# controller.net
KiCad netlist of a schematic drawn in EAGLE
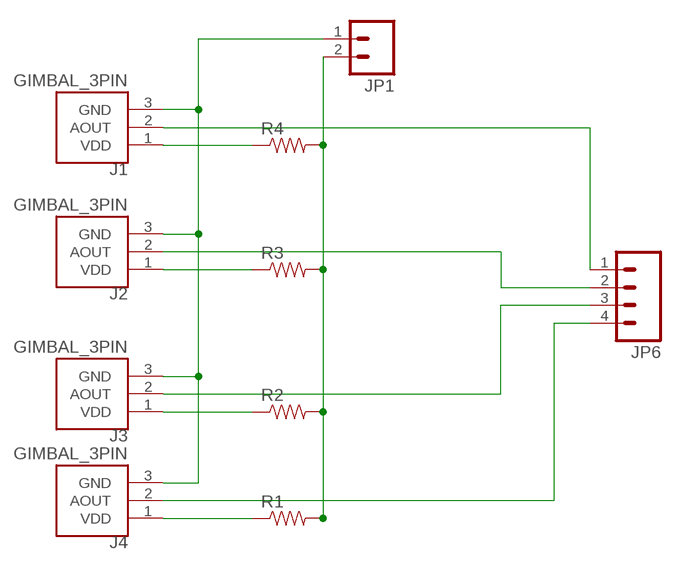
[diagram p0: schematic, sheet 1]

(export (version "E")
  (design (tool "Eeschema 10.0.6"))
  (components
    (comp (ref "J1")
      (value "GIMBAL_3PIN")
      (footprint "eagle-import:JST-3-PTH")
      (libsource (lib "eagle-import") (part "GIMBAL_3PIN"))
    )
    (comp (ref "J2")
      (value "GIMBAL_3PIN")
      (footprint "eagle-import:JST-3-PTH")
      (libsource (lib "eagle-import") (part "GIMBAL_3PIN"))
    )
    (comp (ref "J3")
      (value "GIMBAL_3PIN")
      (footprint "eagle-import:JST-3-PTH")
      (libsource (lib "eagle-import") (part "GIMBAL_3PIN"))
    )
    (comp (ref "J4")
      (value "GIMBAL_3PIN")
      (footprint "eagle-import:JST-3-PTH")
      (libsource (lib "eagle-import") (part "GIMBAL_3PIN"))
    )
    (comp (ref "JP1")
      (value "M02LOCK")
      (footprint "eagle-import:1X02_LOCK")
      (libsource (lib "eagle-import") (part "M02LOCK"))
    )
    (comp (ref "JP6")
      (value "M04PTH")
      (footprint "eagle-import:1X04")
      (libsource (lib "eagle-import") (part "M04PTH"))
    )
    (comp (ref "R1")
      (value "RESISTORPTH-1/6W")
      (footprint "eagle-import:1_6W-RES")
      (libsource (lib "eagle-import") (part "RESISTORPTH-1/6W"))
    )
    (comp (ref "R2")
      (value "RESISTORPTH-1/6W")
      (footprint "eagle-import:1_6W-RES")
      (libsource (lib "eagle-import") (part "RESISTORPTH-1/6W"))
    )
    (comp (ref "R3")
      (value "RESISTORPTH-1/6W")
      (footprint "eagle-import:1_6W-RES")
      (libsource (lib "eagle-import") (part "RESISTORPTH-1/6W"))
    )
    (comp (ref "R4")
      (value "RESISTORPTH-1/6W")
      (footprint "eagle-import:1_6W-RES")
      (libsource (lib "eagle-import") (part "RESISTORPTH-1/6W"))
    )
  )
  (nets
    (net (code "1") (name "Net-(J1-AOUT)") (class "Default")
      (node (ref "J1") (pin "2") (pinfunction "AOUT_2") (pintype "bidirectional"))
      (node (ref "JP6") (pin "1") (pinfunction "1_1") (pintype "passive"))
    )
    (net (code "2") (name "Net-(J1-GND)") (class "Default")
      (node (ref "J1") (pin "3") (pinfunction "GND_3") (pintype "power_in"))
      (node (ref "J2") (pin "3") (pinfunction "GND_3") (pintype "power_in"))
      (node (ref "J3") (pin "3") (pinfunction "GND_3") (pintype "power_in"))
      (node (ref "J4") (pin "3") (pinfunction "GND_3") (pintype "power_in"))
      (node (ref "JP1") (pin "1") (pinfunction "1_1") (pintype "passive"))
    )
    (net (code "3") (name "Net-(J1-VDD)") (class "Default")
      (node (ref "J1") (pin "1") (pinfunction "VDD_1") (pintype "power_in"))
      (node (ref "R4") (pin "1") (pinfunction "1_1") (pintype "passive"))
    )
    (net (code "4") (name "Net-(J2-AOUT)") (class "Default")
      (node (ref "J2") (pin "2") (pinfunction "AOUT_2") (pintype "bidirectional"))
      (node (ref "JP6") (pin "2") (pinfunction "2_2") (pintype "passive"))
    )
    (net (code "5") (name "Net-(J2-VDD)") (class "Default")
      (node (ref "J2") (pin "1") (pinfunction "VDD_1") (pintype "power_in"))
      (node (ref "R3") (pin "1") (pinfunction "1_1") (pintype "passive"))
    )
    (net (code "6") (name "Net-(J3-AOUT)") (class "Default")
      (node (ref "J3") (pin "2") (pinfunction "AOUT_2") (pintype "bidirectional"))
      (node (ref "JP6") (pin "3") (pinfunction "3_3") (pintype "passive"))
    )
    (net (code "7") (name "Net-(J3-VDD)") (class "Default")
      (node (ref "J3") (pin "1") (pinfunction "VDD_1") (pintype "power_in"))
      (node (ref "R2") (pin "1") (pinfunction "1_1") (pintype "passive"))
    )
    (net (code "8") (name "Net-(J4-AOUT)") (class "Default")
      (node (ref "J4") (pin "2") (pinfunction "AOUT_2") (pintype "bidirectional"))
      (node (ref "JP6") (pin "4") (pinfunction "4_4") (pintype "passive"))
    )
    (net (code "9") (name "Net-(J4-VDD)") (class "Default")
      (node (ref "J4") (pin "1") (pinfunction "VDD_1") (pintype "power_in"))
      (node (ref "R1") (pin "1") (pinfunction "1_1") (pintype "passive"))
    )
    (net (code "10") (name "Net-(JP1-Pad2)") (class "Default")
      (node (ref "JP1") (pin "2") (pinfunction "2_2") (pintype "passive"))
      (node (ref "R1") (pin "2") (pinfunction "2_2") (pintype "passive"))
      (node (ref "R2") (pin "2") (pinfunction "2_2") (pintype "passive"))
      (node (ref "R3") (pin "2") (pinfunction "2_2") (pintype "passive"))
      (node (ref "R4") (pin "2") (pinfunction "2_2") (pintype "passive"))
    )
  )
)
